# OpenStage.net
KiCad netlist of a schematic drawn in EAGLE
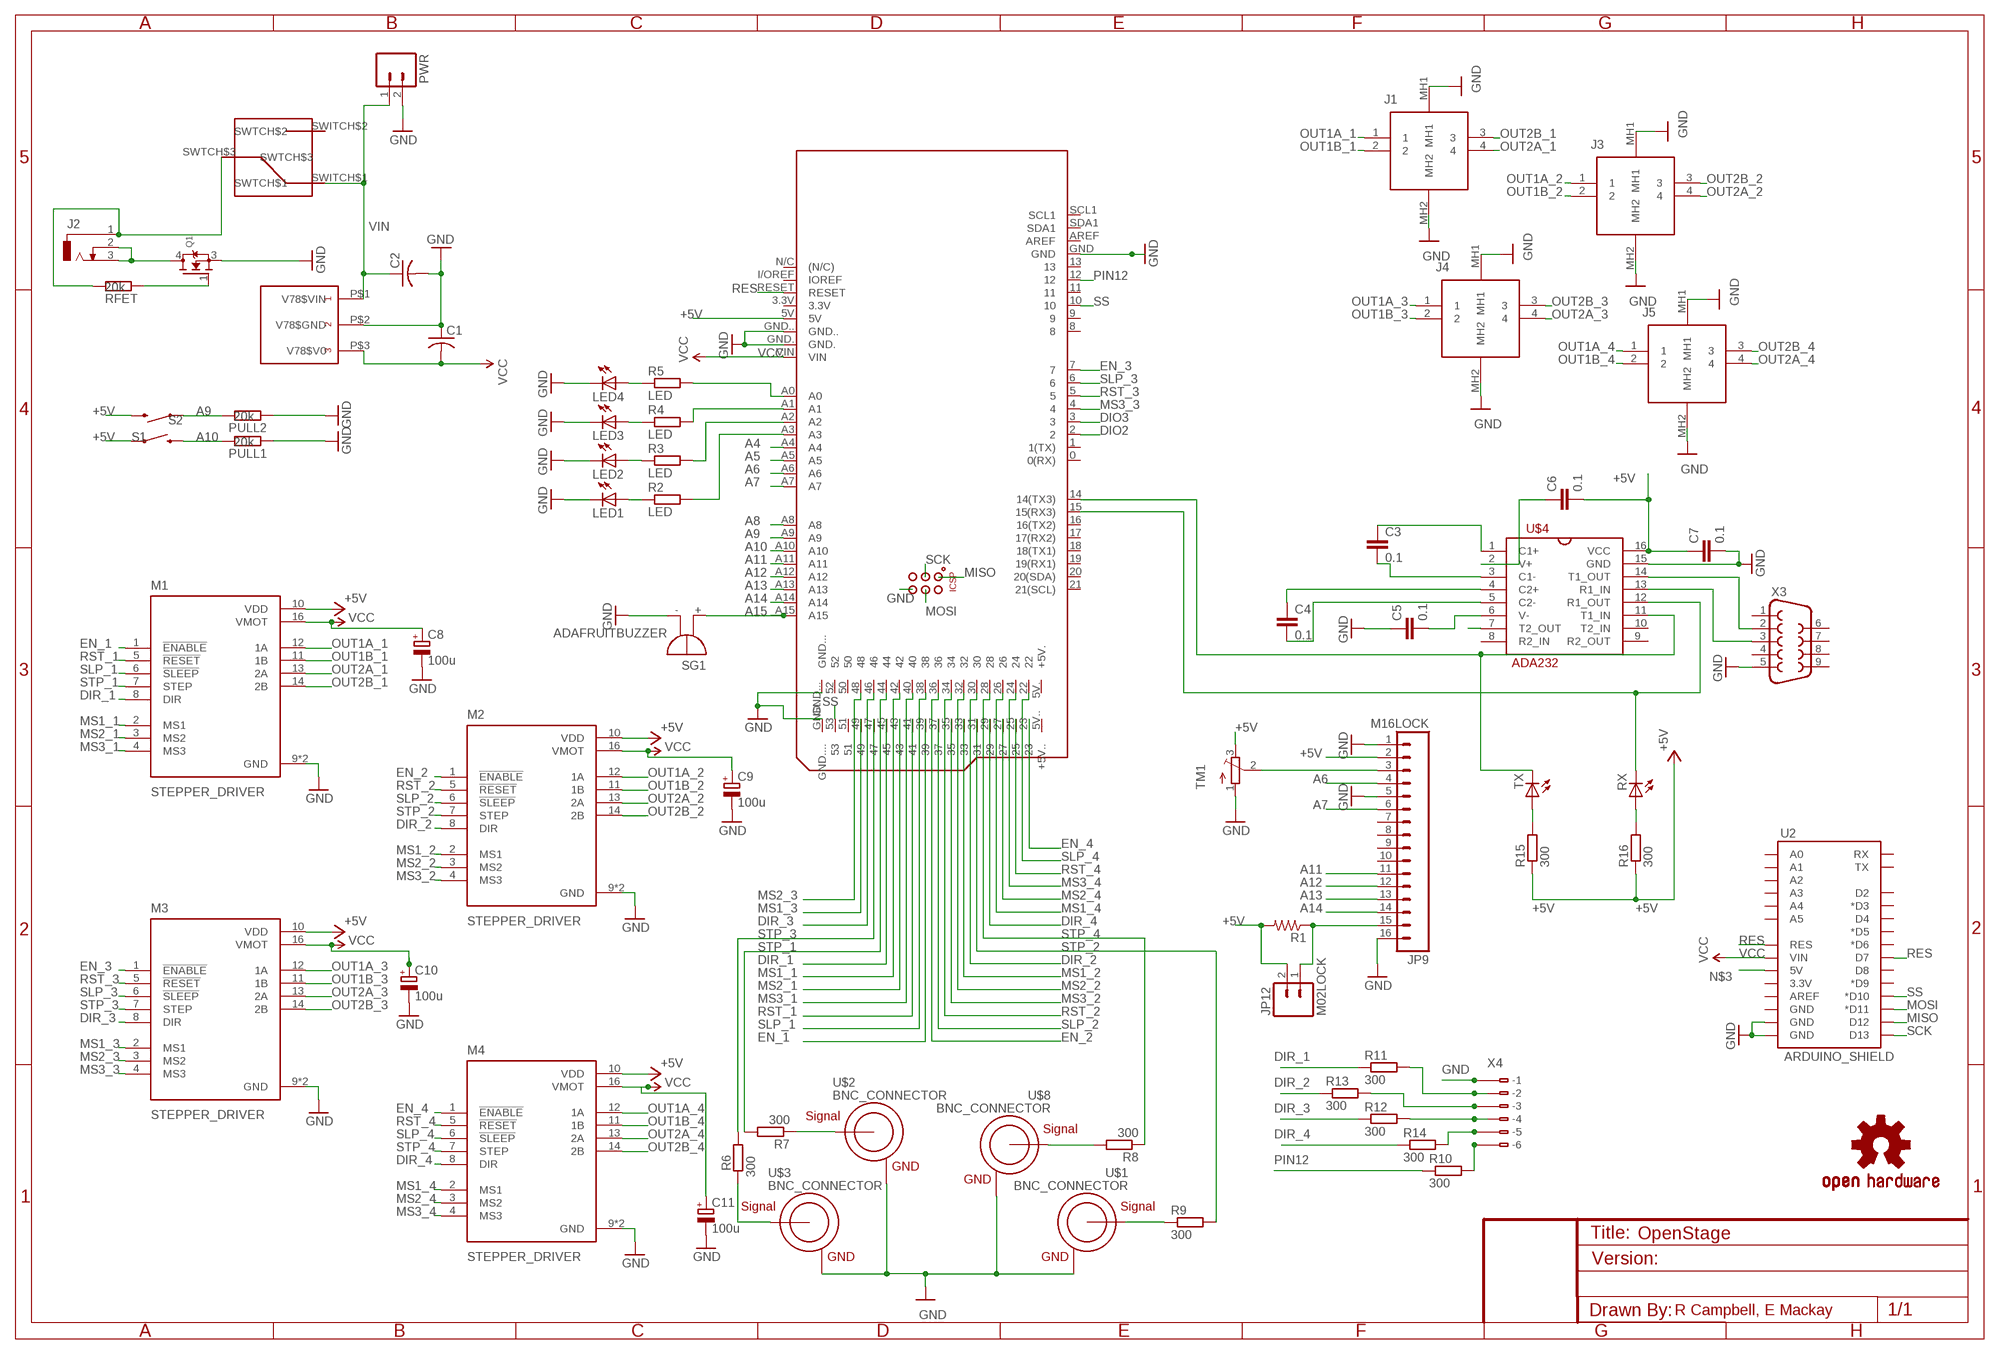
[diagram p0: schematic, sheet 1]

(export (version "E")
  (design (tool "Eeschema 10.0.6"))
  (components
    (comp (ref "C1")
      (value "C-USC1210K")
      (footprint "eagle-import:C1210K")
      (libsource (lib "eagle-import") (part "C-USC1210K"))
    )
    (comp (ref "C2")
      (value "C-USC1210K")
      (footprint "eagle-import:C1210K")
      (libsource (lib "eagle-import") (part "C-USC1210K"))
    )
    (comp (ref "C3")
      (value "0.1")
      (footprint "eagle-import:AXIAL-5MM")
      (libsource (lib "eagle-import") (part "CAP_"))
    )
    (comp (ref "C4")
      (value "0.1")
      (footprint "eagle-import:AXIAL-5MM")
      (libsource (lib "eagle-import") (part "CAP_"))
    )
    (comp (ref "C5")
      (value "0.1")
      (footprint "eagle-import:AXIAL-5MM")
      (libsource (lib "eagle-import") (part "CAP_"))
    )
    (comp (ref "C6")
      (value "0.1")
      (footprint "eagle-import:AXIAL-5MM")
      (libsource (lib "eagle-import") (part "CAP_"))
    )
    (comp (ref "C7")
      (value "0.1")
      (footprint "eagle-import:AXIAL-5MM")
      (libsource (lib "eagle-import") (part "CAP_"))
    )
    (comp (ref "C8")
      (value "100u")
      (footprint "eagle-import:E2,5-5")
      (libsource (lib "eagle-import") (part "CPOL-EUE2.5-5"))
    )
    (comp (ref "C9")
      (value "100u")
      (footprint "eagle-import:E2,5-5")
      (libsource (lib "eagle-import") (part "CPOL-EUE2.5-5"))
    )
    (comp (ref "C10")
      (value "100u")
      (footprint "eagle-import:E2,5-5")
      (libsource (lib "eagle-import") (part "CPOL-EUE2.5-5"))
    )
    (comp (ref "C11")
      (value "100u")
      (footprint "eagle-import:E2,5-5")
      (libsource (lib "eagle-import") (part "CPOL-EUE2.5-5"))
    )
    (comp (ref "J1")
      (value "M8S-04PFFR-SF8001")
      (footprint "eagle-import:M8S04PFFRSF8001")
      (fields (field (name "MOUSER_PART_NUMBER") "523-M8S04PFFRSF8001"))
      (libsource (lib "eagle-import") (part "M8S-04PFFR-SF8001"))
    )
    (comp (ref "J2")
      (value "DCJ0303")
      (footprint "eagle-import:DCJ0303")
      (libsource (lib "eagle-import") (part "DCJ0303"))
    )
    (comp (ref "J3")
      (value "M8S-04PFFR-SF8001")
      (footprint "eagle-import:M8S04PFFRSF8001")
      (fields (field (name "MOUSER_PART_NUMBER") "523-M8S04PFFRSF8001"))
      (libsource (lib "eagle-import") (part "M8S-04PFFR-SF8001"))
    )
    (comp (ref "J4")
      (value "M8S-04PFFR-SF8001")
      (footprint "eagle-import:M8S04PFFRSF8001")
      (fields (field (name "MOUSER_PART_NUMBER") "523-M8S04PFFRSF8001"))
      (libsource (lib "eagle-import") (part "M8S-04PFFR-SF8001"))
    )
    (comp (ref "J5")
      (value "M8S-04PFFR-SF8001")
      (footprint "eagle-import:M8S04PFFRSF8001")
      (fields (field (name "MOUSER_PART_NUMBER") "523-M8S04PFFRSF8001"))
      (libsource (lib "eagle-import") (part "M8S-04PFFR-SF8001"))
    )
    (comp (ref "JP9")
      (value "M16LOCK")
      (footprint "eagle-import:1X16_LOCK")
      (libsource (lib "eagle-import") (part "M16LOCK"))
    )
    (comp (ref "JP12")
      (value "M02LOCK")
      (footprint "eagle-import:1X02_LOCK")
      (libsource (lib "eagle-import") (part "SparkFun-Connectors_M02LOCK"))
    )
    (comp (ref "LED1")
      (value "LED3MM")
      (footprint "eagle-import:LED3MM")
      (libsource (lib "eagle-import") (part "LED3MM"))
    )
    (comp (ref "LED2")
      (value "LED3MM")
      (footprint "eagle-import:LED3MM")
      (libsource (lib "eagle-import") (part "LED3MM"))
    )
    (comp (ref "LED3")
      (value "LED3MM")
      (footprint "eagle-import:LED3MM")
      (libsource (lib "eagle-import") (part "LED3MM"))
    )
    (comp (ref "LED4")
      (value "LED3MM")
      (footprint "eagle-import:LED3MM")
      (libsource (lib "eagle-import") (part "LED3MM"))
    )
    (comp (ref "LOGO1")
      (value "OSHW-LOGOL")
      (footprint "eagle-import:OSHW-LOGO-L")
      (libsource (lib "eagle-import") (part "OSHW-LOGOL"))
    )
    (comp (ref "M1")
      (value "STEPPER_DRIVER")
      (footprint "eagle-import:POLOLU_CARRIER")
      (fields (field (name "MF") "Pololu") (field (name "MP") "A4988 STEPPER MOTOR DRIVER CARRIER"))
      (libsource (lib "eagle-import") (part "STEPPER_DRIVER"))
    )
    (comp (ref "M2")
      (value "STEPPER_DRIVER")
      (footprint "eagle-import:POLOLU_CARRIER")
      (fields (field (name "MF") "Pololu") (field (name "MP") "A4988 STEPPER MOTOR DRIVER CARRIER"))
      (libsource (lib "eagle-import") (part "STEPPER_DRIVER"))
    )
    (comp (ref "M3")
      (value "STEPPER_DRIVER")
      (footprint "eagle-import:POLOLU_CARRIER")
      (fields (field (name "MF") "Pololu") (field (name "MP") "A4988 STEPPER MOTOR DRIVER CARRIER"))
      (libsource (lib "eagle-import") (part "STEPPER_DRIVER"))
    )
    (comp (ref "M4")
      (value "STEPPER_DRIVER")
      (footprint "eagle-import:POLOLU_CARRIER")
      (fields (field (name "MF") "Pololu") (field (name "MP") "A4988 STEPPER MOTOR DRIVER CARRIER"))
      (libsource (lib "eagle-import") (part "STEPPER_DRIVER"))
    )
    (comp (ref "PCB2")
      (value "ARDUINO_MEGA_ROB")
      (footprint "eagle-import:ARDUINO_MEGA_ROB")
      (libsource (lib "eagle-import") (part "ARDUINO_MEGA_ROB"))
    )
    (comp (ref "PULL1")
      (value "20k")
      (footprint "eagle-import:R3216")
      (libsource (lib "eagle-import") (part "R-EU_R3216"))
    )
    (comp (ref "PULL2")
      (value "20k")
      (footprint "eagle-import:R3216")
      (libsource (lib "eagle-import") (part "R-EU_R3216"))
    )
    (comp (ref "PWR")
      (value "M02PTH")
      (footprint "eagle-import:1X02")
      (libsource (lib "eagle-import") (part "M02PTH"))
    )
    (comp (ref "Q1")
      (value "MOSFET-N_TO252")
      (footprint "eagle-import:TO252")
      (libsource (lib "eagle-import") (part "MOSFET-N_TO252"))
    )
    (comp (ref "R1")
      (value "R-US_0204/7")
      (footprint "eagle-import:0204_7")
      (libsource (lib "eagle-import") (part "R-US_0204/7"))
    )
    (comp (ref "R2")
      (value "LED")
      (footprint "eagle-import:R3216")
      (libsource (lib "eagle-import") (part "R-EU_R3216"))
    )
    (comp (ref "R3")
      (value "LED")
      (footprint "eagle-import:R3216")
      (libsource (lib "eagle-import") (part "R-EU_R3216"))
    )
    (comp (ref "R4")
      (value "LED")
      (footprint "eagle-import:R3216")
      (libsource (lib "eagle-import") (part "R-EU_R3216"))
    )
    (comp (ref "R5")
      (value "LED")
      (footprint "eagle-import:R3216")
      (libsource (lib "eagle-import") (part "R-EU_R3216"))
    )
    (comp (ref "R6")
      (value "300")
      (footprint "eagle-import:R3216")
      (libsource (lib "eagle-import") (part "R-EU_R3216"))
    )
    (comp (ref "R7")
      (value "300")
      (footprint "eagle-import:R3216")
      (libsource (lib "eagle-import") (part "R-EU_R3216"))
    )
    (comp (ref "R8")
      (value "300")
      (footprint "eagle-import:R3216")
      (libsource (lib "eagle-import") (part "R-EU_R3216"))
    )
    (comp (ref "R9")
      (value "300")
      (footprint "eagle-import:R3216")
      (libsource (lib "eagle-import") (part "R-EU_R3216"))
    )
    (comp (ref "R10")
      (value "300")
      (footprint "eagle-import:R3216")
      (libsource (lib "eagle-import") (part "R-EU_R3216"))
    )
    (comp (ref "R11")
      (value "300")
      (footprint "eagle-import:R3216")
      (libsource (lib "eagle-import") (part "R-EU_R3216"))
    )
    (comp (ref "R12")
      (value "300")
      (footprint "eagle-import:R3216")
      (libsource (lib "eagle-import") (part "R-EU_R3216"))
    )
    (comp (ref "R13")
      (value "300")
      (footprint "eagle-import:R3216")
      (libsource (lib "eagle-import") (part "R-EU_R3216"))
    )
    (comp (ref "R14")
      (value "300")
      (footprint "eagle-import:R3216")
      (libsource (lib "eagle-import") (part "R-EU_R3216"))
    )
    (comp (ref "R15")
      (value "300")
      (footprint "eagle-import:R3216")
      (libsource (lib "eagle-import") (part "R-EU_R3216"))
    )
    (comp (ref "R16")
      (value "300")
      (footprint "eagle-import:R3216")
      (libsource (lib "eagle-import") (part "R-EU_R3216"))
    )
    (comp (ref "RFET")
      (value "20k")
      (footprint "eagle-import:R3216")
      (libsource (lib "eagle-import") (part "R-EU_R3216"))
    )
    (comp (ref "RX")
      (value "LED3MM")
      (footprint "eagle-import:LED3MM")
      (libsource (lib "eagle-import") (part "LED3MM"))
    )
    (comp (ref "S1")
      (value "SWITCH-MOMENTARY-212MM")
      (footprint "eagle-import:TACTILE-PTH-12MM")
      (libsource (lib "eagle-import") (part "SWITCH-MOMENTARY-212MM"))
    )
    (comp (ref "S2")
      (value "SWITCH-MOMENTARY-212MM")
      (footprint "eagle-import:TACTILE-PTH-12MM")
      (libsource (lib "eagle-import") (part "SWITCH-MOMENTARY-212MM"))
    )
    (comp (ref "SG1")
      (value "ADAFRUITBUZZER")
      (footprint "eagle-import:BMT1205XH7.5")
      (libsource (lib "eagle-import") (part "ADAFRUITBUZZER"))
    )
    (comp (ref "TM1")
      (value "TRIMPOT3386")
      (footprint "eagle-import:TRIM-3386")
      (libsource (lib "eagle-import") (part "TRIMPOT3386"))
    )
    (comp (ref "TX")
      (value "LED3MM")
      (footprint "eagle-import:LED3MM")
      (libsource (lib "eagle-import") (part "LED3MM"))
    )
    (comp (ref "U$1")
      (value "BNC_CONNECTOR")
      (footprint "eagle-import:BNC_CONNECTOR")
      (libsource (lib "eagle-import") (part "BNC_CONNECTOR"))
    )
    (comp (ref "U$2")
      (value "BNC_CONNECTOR")
      (footprint "eagle-import:BNC_CONNECTOR")
      (libsource (lib "eagle-import") (part "BNC_CONNECTOR"))
    )
    (comp (ref "U$3")
      (value "BNC_CONNECTOR")
      (footprint "eagle-import:BNC_CONNECTOR")
      (libsource (lib "eagle-import") (part "BNC_CONNECTOR"))
    )
    (comp (ref "U$4")
      (value "ADA232")
      (footprint "eagle-import:DIL16")
      (libsource (lib "eagle-import") (part "ADA232"))
    )
    (comp (ref "U$5")
      (value "V78XX-1000")
      (footprint "eagle-import:V78XX-1000")
      (libsource (lib "eagle-import") (part "V78XX-1000"))
    )
    (comp (ref "U$6")
      (value "SLIDING_SWITCH_0.185")
      (footprint "eagle-import:SLIDING_SWITCH_0.185")
      (libsource (lib "eagle-import") (part "SLIDING_SWITCH_0.185"))
    )
    (comp (ref "U$8")
      (value "BNC_CONNECTOR")
      (footprint "eagle-import:BNC_CONNECTOR")
      (libsource (lib "eagle-import") (part "BNC_CONNECTOR"))
    )
    (comp (ref "U2")
      (value "ARDUINO_SHIELD")
      (footprint "eagle-import:DUEMILANOVE_VIAS")
      (libsource (lib "eagle-import") (part "ARDUINO_SHIELDNO_SILK"))
    )
    (comp (ref "X3")
      (value "DB9FEMALE")
      (footprint "eagle-import:DB9")
      (libsource (lib "eagle-import") (part "DB9FEMALE"))
    )
    (comp (ref "X4")
      (value "233-206")
      (footprint "eagle-import:233-206")
      (libsource (lib "eagle-import") (part "233-206"))
    )
  )
  (nets
    (net (code "1") (name "+5V") (class "Default")
      (node (ref "C6") (pin "P$2") (pinfunction "2_P$2") (pintype "passive"))
      (node (ref "C7") (pin "P$1") (pinfunction "1_P$1") (pintype "passive"))
      (node (ref "JP12") (pin "2") (pinfunction "2_2") (pintype "passive"))
      (node (ref "JP9") (pin "2") (pinfunction "2_2") (pintype "passive"))
      (node (ref "M1") (pin "10") (pinfunction "VDD_10") (pintype "power_in"))
      (node (ref "M2") (pin "10") (pinfunction "VDD_10") (pintype "power_in"))
      (node (ref "M3") (pin "10") (pinfunction "VDD_10") (pintype "power_in"))
      (node (ref "M4") (pin "10") (pinfunction "VDD_10") (pintype "power_in"))
      (node (ref "PCB2") (pin "5V") (pinfunction "5V_5V") (pintype "bidirectional"))
      (node (ref "R1") (pin "2") (pinfunction "2_2") (pintype "passive"))
      (node (ref "R15") (pin "1") (pinfunction "1_1") (pintype "passive"))
      (node (ref "R16") (pin "1") (pinfunction "1_1") (pintype "passive"))
      (node (ref "S1") (pin "1") (pinfunction "1_1") (pintype "passive"))
      (node (ref "S2") (pin "3") (pinfunction "2_3") (pintype "passive"))
      (node (ref "TM1") (pin "3") (pinfunction "E_3") (pintype "passive"))
      (node (ref "U$4") (pin "16") (pinfunction "VCC_16") (pintype "bidirectional"))
    )
    (net (code "2") (name "/A4") (class "Default")
      (node (ref "PCB2") (pin "A4") (pinfunction "A4_A4") (pintype "bidirectional"))
    )
    (net (code "3") (name "/A5") (class "Default")
      (node (ref "PCB2") (pin "A5") (pinfunction "A5_A5") (pintype "bidirectional"))
    )
    (net (code "4") (name "/A6") (class "Default")
      (node (ref "JP9") (pin "4") (pinfunction "4_4") (pintype "passive"))
      (node (ref "PCB2") (pin "A6") (pinfunction "A6_A6") (pintype "bidirectional"))
    )
    (net (code "5") (name "/A7") (class "Default")
      (node (ref "JP9") (pin "6") (pinfunction "6_6") (pintype "passive"))
      (node (ref "PCB2") (pin "A7") (pinfunction "A7_A7") (pintype "bidirectional"))
    )
    (net (code "6") (name "/A8") (class "Default")
      (node (ref "PCB2") (pin "A8") (pinfunction "A8_A8") (pintype "bidirectional"))
    )
    (net (code "7") (name "/A9") (class "Default")
      (node (ref "PCB2") (pin "A9") (pinfunction "A9_A9") (pintype "bidirectional"))
      (node (ref "PULL2") (pin "2") (pinfunction "2_2") (pintype "passive"))
      (node (ref "S2") (pin "1") (pinfunction "1_1") (pintype "passive"))
    )
    (net (code "8") (name "/A10") (class "Default")
      (node (ref "PCB2") (pin "A10") (pinfunction "A10_A10") (pintype "bidirectional"))
      (node (ref "PULL1") (pin "2") (pinfunction "2_2") (pintype "passive"))
      (node (ref "S1") (pin "3") (pinfunction "2_3") (pintype "passive"))
    )
    (net (code "9") (name "/A11") (class "Default")
      (node (ref "JP9") (pin "11") (pinfunction "11_11") (pintype "passive"))
      (node (ref "PCB2") (pin "A11") (pinfunction "A11_A11") (pintype "bidirectional"))
    )
    (net (code "10") (name "/A12") (class "Default")
      (node (ref "JP9") (pin "12") (pinfunction "12_12") (pintype "passive"))
      (node (ref "PCB2") (pin "A12") (pinfunction "A12_A12") (pintype "bidirectional"))
    )
    (net (code "11") (name "/A13") (class "Default")
      (node (ref "JP9") (pin "13") (pinfunction "13_13") (pintype "passive"))
      (node (ref "PCB2") (pin "A13") (pinfunction "A13_A13") (pintype "bidirectional"))
    )
    (net (code "12") (name "/A14") (class "Default")
      (node (ref "JP9") (pin "14") (pinfunction "14_14") (pintype "passive"))
      (node (ref "PCB2") (pin "A14") (pinfunction "A14_A14") (pintype "bidirectional"))
    )
    (net (code "13") (name "/A15") (class "Default")
      (node (ref "PCB2") (pin "A15") (pinfunction "A15_A15") (pintype "bidirectional"))
      (node (ref "SG1") (pin "+") (pinfunction "+_+") (pintype "passive"))
    )
    (net (code "14") (name "/DIO2") (class "Default")
      (node (ref "PCB2") (pin "2") (pinfunction "2_2") (pintype "bidirectional"))
    )
    (net (code "15") (name "/DIO3") (class "Default")
      (node (ref "PCB2") (pin "3") (pinfunction "3_3") (pintype "bidirectional"))
    )
    (net (code "16") (name "/DIR_1") (class "Default")
      (node (ref "M1") (pin "8") (pinfunction "DIR_8") (pintype "input"))
      (node (ref "PCB2") (pin "45") (pinfunction "45_45") (pintype "bidirectional"))
      (node (ref "R11") (pin "1") (pinfunction "1_1") (pintype "passive"))
    )
    (net (code "17") (name "/DIR_2") (class "Default")
      (node (ref "M2") (pin "8") (pinfunction "DIR_8") (pintype "input"))
      (node (ref "PCB2") (pin "30") (pinfunction "30_30") (pintype "bidirectional"))
      (node (ref "R13") (pin "1") (pinfunction "1_1") (pintype "passive"))
    )
    (net (code "18") (name "/DIR_3") (class "Default")
      (node (ref "M3") (pin "8") (pinfunction "DIR_8") (pintype "input"))
      (node (ref "PCB2") (pin "46") (pinfunction "46_46") (pintype "bidirectional"))
      (node (ref "R12") (pin "1") (pinfunction "1_1") (pintype "passive"))
    )
    (net (code "19") (name "/DIR_4") (class "Default")
      (node (ref "M4") (pin "8") (pinfunction "DIR_8") (pintype "input"))
      (node (ref "PCB2") (pin "29") (pinfunction "29_29") (pintype "bidirectional"))
      (node (ref "R14") (pin "1") (pinfunction "1_1") (pintype "passive"))
    )
    (net (code "20") (name "/EN_1") (class "Default")
      (node (ref "M1") (pin "1") (pinfunction "~{ENABLE}_1") (pintype "input"))
      (node (ref "PCB2") (pin "39") (pinfunction "39_39") (pintype "bidirectional"))
    )
    (net (code "21") (name "/EN_2") (class "Default")
      (node (ref "M2") (pin "1") (pinfunction "~{ENABLE}_1") (pintype "input"))
      (node (ref "PCB2") (pin "36") (pinfunction "36_36") (pintype "bidirectional"))
    )
    (net (code "22") (name "/EN_3") (class "Default")
      (node (ref "M3") (pin "1") (pinfunction "~{ENABLE}_1") (pintype "input"))
      (node (ref "PCB2") (pin "7") (pinfunction "7_7") (pintype "bidirectional"))
    )
    (net (code "23") (name "/EN_4") (class "Default")
      (node (ref "M4") (pin "1") (pinfunction "~{ENABLE}_1") (pintype "input"))
      (node (ref "PCB2") (pin "23") (pinfunction "23_23") (pintype "bidirectional"))
    )
    (net (code "24") (name "/MISO") (class "Default")
      (node (ref "PCB2") (pin "MISO") (pinfunction "MISO_MISO") (pintype "bidirectional"))
      (node (ref "U2") (pin "D12") (pinfunction "D12_D12") (pintype "bidirectional"))
    )
    (net (code "25") (name "/MOSI") (class "Default")
      (node (ref "PCB2") (pin "MOSI") (pinfunction "MOSI_MOSI") (pintype "bidirectional"))
      (node (ref "U2") (pin "D11") (pinfunction "*D11_D11") (pintype "bidirectional"))
    )
    (net (code "26") (name "/MS1_1") (class "Default")
      (node (ref "M1") (pin "2") (pinfunction "MS1_2") (pintype "input"))
      (node (ref "PCB2") (pin "42") (pinfunction "42_42") (pintype "bidirectional"))
    )
    (net (code "27") (name "/MS1_2") (class "Default")
      (node (ref "M2") (pin "2") (pinfunction "MS1_2") (pintype "input"))
      (node (ref "PCB2") (pin "33") (pinfunction "33_33") (pintype "bidirectional"))
    )
    (net (code "28") (name "/MS1_3") (class "Default")
      (node (ref "M3") (pin "2") (pinfunction "MS1_2") (pintype "input"))
      (node (ref "PCB2") (pin "49") (pinfunction "49_49") (pintype "bidirectional"))
    )
    (net (code "29") (name "/MS1_4") (class "Default")
      (node (ref "M4") (pin "2") (pinfunction "MS1_2") (pintype "input"))
      (node (ref "PCB2") (pin "26") (pinfunction "26_26") (pintype "bidirectional"))
    )
    (net (code "30") (name "/MS2_1") (class "Default")
      (node (ref "M1") (pin "3") (pinfunction "MS2_3") (pintype "input"))
      (node (ref "PCB2") (pin "43") (pinfunction "43_43") (pintype "bidirectional"))
    )
    (net (code "31") (name "/MS2_2") (class "Default")
      (node (ref "M2") (pin "3") (pinfunction "MS2_3") (pintype "input"))
      (node (ref "PCB2") (pin "32") (pinfunction "32_32") (pintype "bidirectional"))
    )
    (net (code "32") (name "/MS2_3") (class "Default")
      (node (ref "M3") (pin "3") (pinfunction "MS2_3") (pintype "input"))
      (node (ref "PCB2") (pin "48") (pinfunction "48_48") (pintype "bidirectional"))
    )
    (net (code "33") (name "/MS2_4") (class "Default")
      (node (ref "M4") (pin "3") (pinfunction "MS2_3") (pintype "input"))
      (node (ref "PCB2") (pin "27") (pinfunction "27_27") (pintype "bidirectional"))
    )
    (net (code "34") (name "/MS3_1") (class "Default")
      (node (ref "M1") (pin "4") (pinfunction "MS3_4") (pintype "input"))
      (node (ref "PCB2") (pin "40") (pinfunction "40_40") (pintype "bidirectional"))
    )
    (net (code "35") (name "/MS3_2") (class "Default")
      (node (ref "M2") (pin "4") (pinfunction "MS3_4") (pintype "input"))
      (node (ref "PCB2") (pin "35") (pinfunction "35_35") (pintype "bidirectional"))
    )
    (net (code "36") (name "/MS3_3") (class "Default")
      (node (ref "M3") (pin "4") (pinfunction "MS3_4") (pintype "input"))
      (node (ref "PCB2") (pin "4") (pinfunction "4_4") (pintype "bidirectional"))
    )
    (net (code "37") (name "/MS3_4") (class "Default")
      (node (ref "M4") (pin "4") (pinfunction "MS3_4") (pintype "input"))
      (node (ref "PCB2") (pin "24") (pinfunction "24_24") (pintype "bidirectional"))
    )
    (net (code "38") (name "/N$3") (class "Default")
      (node (ref "U2") (pin "5V") (pinfunction "5V_5V") (pintype "bidirectional"))
    )
    (net (code "39") (name "/OUT1A_1") (class "Default")
      (node (ref "J1") (pin "1") (pinfunction "1_1") (pintype "bidirectional"))
      (node (ref "M1") (pin "12") (pinfunction "1A_12") (pintype "output"))
    )
    (net (code "40") (name "/OUT1A_2") (class "Default")
      (node (ref "J3") (pin "1") (pinfunction "1_1") (pintype "bidirectional"))
      (node (ref "M2") (pin "12") (pinfunction "1A_12") (pintype "output"))
    )
    (net (code "41") (name "/OUT1A_3") (class "Default")
      (node (ref "J4") (pin "1") (pinfunction "1_1") (pintype "bidirectional"))
      (node (ref "M3") (pin "12") (pinfunction "1A_12") (pintype "output"))
    )
    (net (code "42") (name "/OUT1A_4") (class "Default")
      (node (ref "J5") (pin "1") (pinfunction "1_1") (pintype "bidirectional"))
      (node (ref "M4") (pin "12") (pinfunction "1A_12") (pintype "output"))
    )
    (net (code "43") (name "/OUT1B_1") (class "Default")
      (node (ref "J1") (pin "2") (pinfunction "2_2") (pintype "bidirectional"))
      (node (ref "M1") (pin "11") (pinfunction "1B_11") (pintype "output"))
    )
    (net (code "44") (name "/OUT1B_2") (class "Default")
      (node (ref "J3") (pin "2") (pinfunction "2_2") (pintype "bidirectional"))
      (node (ref "M2") (pin "11") (pinfunction "1B_11") (pintype "output"))
    )
    (net (code "45") (name "/OUT1B_3") (class "Default")
      (node (ref "J4") (pin "2") (pinfunction "2_2") (pintype "bidirectional"))
      (node (ref "M3") (pin "11") (pinfunction "1B_11") (pintype "output"))
    )
    (net (code "46") (name "/OUT1B_4") (class "Default")
      (node (ref "J5") (pin "2") (pinfunction "2_2") (pintype "bidirectional"))
      (node (ref "M4") (pin "11") (pinfunction "1B_11") (pintype "output"))
    )
    (net (code "47") (name "/OUT2A_1") (class "Default")
      (node (ref "J1") (pin "4") (pinfunction "4_4") (pintype "bidirectional"))
      (node (ref "M1") (pin "13") (pinfunction "2A_13") (pintype "output"))
    )
    (net (code "48") (name "/OUT2A_2") (class "Default")
      (node (ref "J3") (pin "4") (pinfunction "4_4") (pintype "bidirectional"))
      (node (ref "M2") (pin "13") (pinfunction "2A_13") (pintype "output"))
    )
    (net (code "49") (name "/OUT2A_3") (class "Default")
      (node (ref "J4") (pin "4") (pinfunction "4_4") (pintype "bidirectional"))
      (node (ref "M3") (pin "13") (pinfunction "2A_13") (pintype "output"))
    )
    (net (code "50") (name "/OUT2A_4") (class "Default")
      (node (ref "J5") (pin "4") (pinfunction "4_4") (pintype "bidirectional"))
      (node (ref "M4") (pin "13") (pinfunction "2A_13") (pintype "output"))
    )
    (net (code "51") (name "/OUT2B_1") (class "Default")
      (node (ref "J1") (pin "3") (pinfunction "3_3") (pintype "bidirectional"))
      (node (ref "M1") (pin "14") (pinfunction "2B_14") (pintype "output"))
    )
    (net (code "52") (name "/OUT2B_2") (class "Default")
      (node (ref "J3") (pin "3") (pinfunction "3_3") (pintype "bidirectional"))
      (node (ref "M2") (pin "14") (pinfunction "2B_14") (pintype "output"))
    )
    (net (code "53") (name "/OUT2B_3") (class "Default")
      (node (ref "J4") (pin "3") (pinfunction "3_3") (pintype "bidirectional"))
      (node (ref "M3") (pin "14") (pinfunction "2B_14") (pintype "output"))
    )
    (net (code "54") (name "/OUT2B_4") (class "Default")
      (node (ref "J5") (pin "3") (pinfunction "3_3") (pintype "bidirectional"))
      (node (ref "M4") (pin "14") (pinfunction "2B_14") (pintype "output"))
    )
    (net (code "55") (name "/PIN12") (class "Default")
      (node (ref "PCB2") (pin "12") (pinfunction "12_12") (pintype "bidirectional"))
      (node (ref "R10") (pin "1") (pinfunction "1_1") (pintype "passive"))
    )
    (net (code "56") (name "/RES") (class "Default")
      (node (ref "PCB2") (pin "RESET") (pinfunction "RESET_RESET") (pintype "bidirectional"))
      (node (ref "U2") (pin "D7") (pinfunction "D7_D7") (pintype "bidirectional"))
      (node (ref "U2") (pin "RES") (pinfunction "RES_RES") (pintype "bidirectional"))
    )
    (net (code "57") (name "/RST_1") (class "Default")
      (node (ref "M1") (pin "5") (pinfunction "~{RESET}_5") (pintype "input"))
      (node (ref "PCB2") (pin "41") (pinfunction "41_41") (pintype "bidirectional"))
    )
    (net (code "58") (name "/RST_2") (class "Default")
      (node (ref "M2") (pin "5") (pinfunction "~{RESET}_5") (pintype "input"))
      (node (ref "PCB2") (pin "34") (pinfunction "34_34") (pintype "bidirectional"))
    )
    (net (code "59") (name "/RST_3") (class "Default")
      (node (ref "M3") (pin "5") (pinfunction "~{RESET}_5") (pintype "input"))
      (node (ref "PCB2") (pin "5") (pinfunction "5_5") (pintype "bidirectional"))
    )
    (net (code "60") (name "/RST_4") (class "Default")
      (node (ref "M4") (pin "5") (pinfunction "~{RESET}_5") (pintype "input"))
      (node (ref "PCB2") (pin "25") (pinfunction "25_25") (pintype "bidirectional"))
    )
    (net (code "61") (name "/SCK") (class "Default")
      (node (ref "PCB2") (pin "SCK") (pinfunction "SCK_SCK") (pintype "bidirectional"))
      (node (ref "U2") (pin "D13") (pinfunction "D13_D13") (pintype "bidirectional"))
    )
    (net (code "62") (name "/SLP_1") (class "Default")
      (node (ref "M1") (pin "6") (pinfunction "~{SLEEP}_6") (pintype "input"))
      (node (ref "PCB2") (pin "38") (pinfunction "38_38") (pintype "bidirectional"))
    )
    (net (code "63") (name "/SLP_2") (class "Default")
      (node (ref "M2") (pin "6") (pinfunction "~{SLEEP}_6") (pintype "input"))
      (node (ref "PCB2") (pin "37") (pinfunction "37_37") (pintype "bidirectional"))
    )
    (net (code "64") (name "/SLP_3") (class "Default")
      (node (ref "M3") (pin "6") (pinfunction "~{SLEEP}_6") (pintype "input"))
      (node (ref "PCB2") (pin "6") (pinfunction "6_6") (pintype "bidirectional"))
    )
    (net (code "65") (name "/SLP_4") (class "Default")
      (node (ref "M4") (pin "6") (pinfunction "~{SLEEP}_6") (pintype "input"))
      (node (ref "PCB2") (pin "22") (pinfunction "22_22") (pintype "bidirectional"))
    )
    (net (code "66") (name "/SS") (class "Default")
      (node (ref "PCB2") (pin "10") (pinfunction "10_10") (pintype "bidirectional"))
      (node (ref "PCB2") (pin "53") (pinfunction "53_53") (pintype "bidirectional"))
      (node (ref "U2") (pin "D10") (pinfunction "*D10_D10") (pintype "bidirectional"))
    )
    (net (code "67") (name "/STP_1") (class "Default")
      (node (ref "M1") (pin "7") (pinfunction "STEP_7") (pintype "input"))
      (node (ref "PCB2") (pin "44") (pinfunction "44_44") (pintype "bidirectional"))
      (node (ref "R7") (pin "2") (pinfunction "2_2") (pintype "passive"))
    )
    (net (code "68") (name "/STP_2") (class "Default")
      (node (ref "M2") (pin "7") (pinfunction "STEP_7") (pintype "input"))
      (node (ref "PCB2") (pin "31") (pinfunction "31_31") (pintype "bidirectional"))
      (node (ref "R9") (pin "2") (pinfunction "2_2") (pintype "passive"))
    )
    (net (code "69") (name "/STP_3") (class "Default")
      (node (ref "M3") (pin "7") (pinfunction "STEP_7") (pintype "input"))
      (node (ref "PCB2") (pin "47") (pinfunction "47_47") (pintype "bidirectional"))
      (node (ref "R6") (pin "2") (pinfunction "2_2") (pintype "passive"))
    )
    (net (code "70") (name "/STP_4") (class "Default")
      (node (ref "M4") (pin "7") (pinfunction "STEP_7") (pintype "input"))
      (node (ref "PCB2") (pin "28") (pinfunction "28_28") (pintype "bidirectional"))
      (node (ref "R8") (pin "1") (pinfunction "1_1") (pintype "passive"))
    )
    (net (code "71") (name "/VIN") (class "Default")
      (node (ref "C2") (pin "1") (pinfunction "1_1") (pintype "passive"))
      (node (ref "PWR") (pin "1") (pinfunction "1_1") (pintype "passive"))
      (node (ref "U$5") (pin "P$1") (pinfunction "V78$VIN_P$1") (pintype "bidirectional"))
      (node (ref "U$6") (pin "SWITCH$1") (pinfunction "SWTCH$1_SWITCH$1") (pintype "bidirectional"))
    )
    (net (code "72") (name "GND") (class "Default")
      (node (ref "C1") (pin "1") (pinfunction "1_1") (pintype "passive"))
      (node (ref "C10") (pin "-") (pinfunction "-_-") (pintype "passive"))
      (node (ref "C11") (pin "-") (pinfunction "-_-") (pintype "passive"))
      (node (ref "C2") (pin "2") (pinfunction "2_2") (pintype "passive"))
      (node (ref "C5") (pin "P$1") (pinfunction "1_P$1") (pintype "passive"))
      (node (ref "C7") (pin "P$2") (pinfunction "2_P$2") (pintype "passive"))
      (node (ref "C8") (pin "-") (pinfunction "-_-") (pintype "passive"))
      (node (ref "C9") (pin "-") (pinfunction "-_-") (pintype "passive"))
      (node (ref "J1") (pin "MH1") (pinfunction "MH1_MH1") (pintype "bidirectional"))
      (node (ref "J1") (pin "MH2") (pinfunction "MH2_MH2") (pintype "bidirectional"))
      (node (ref "J3") (pin "MH1") (pinfunction "MH1_MH1") (pintype "bidirectional"))
      (node (ref "J3") (pin "MH2") (pinfunction "MH2_MH2") (pintype "bidirectional"))
      (node (ref "J4") (pin "MH1") (pinfunction "MH1_MH1") (pintype "bidirectional"))
      (node (ref "J4") (pin "MH2") (pinfunction "MH2_MH2") (pintype "bidirectional"))
      (node (ref "J5") (pin "MH1") (pinfunction "MH1_MH1") (pintype "bidirectional"))
      (node (ref "J5") (pin "MH2") (pinfunction "MH2_MH2") (pintype "bidirectional"))
      (node (ref "JP9") (pin "1") (pinfunction "1_1") (pintype "passive"))
      (node (ref "JP9") (pin "16") (pinfunction "16_16") (pintype "passive"))
      (node (ref "JP9") (pin "5") (pinfunction "5_5") (pintype "passive"))
      (node (ref "LED1") (pin "K") (pinfunction "C_K") (pintype "passive"))
      (node (ref "LED2") (pin "K") (pinfunction "C_K") (pintype "passive"))
      (node (ref "LED3") (pin "K") (pinfunction "C_K") (pintype "passive"))
      (node (ref "LED4") (pin "K") (pinfunction "C_K") (pintype "passive"))
      (node (ref "M1") (pin "15") (pinfunction "GND_15") (pintype "power_in"))
      (node (ref "M1") (pin "9") (pinfunction "GND_9") (pintype "power_in"))
      (node (ref "M2") (pin "15") (pinfunction "GND_15") (pintype "power_in"))
      (node (ref "M2") (pin "9") (pinfunction "GND_9") (pintype "power_in"))
      (node (ref "M3") (pin "15") (pinfunction "GND_15") (pintype "power_in"))
      (node (ref "M3") (pin "9") (pinfunction "GND_9") (pintype "power_in"))
      (node (ref "M4") (pin "15") (pinfunction "GND_15") (pintype "power_in"))
      (node (ref "M4") (pin "9") (pinfunction "GND_9") (pintype "power_in"))
      (node (ref "PCB2") (pin "GND") (pinfunction "GND_GND") (pintype "bidirectional"))
      (node (ref "PCB2") (pin "GND.") (pinfunction "GND._GND.") (pintype "bidirectional"))
      (node (ref "PCB2") (pin "GND..") (pinfunction "GND.._GND..") (pintype "bidirectional"))
      (node (ref "PCB2") (pin "GND...") (pinfunction "GND..._GND...") (pintype "bidirectional"))
      (node (ref "PCB2") (pin "GND....") (pinfunction "GND...._GND....") (pintype "bidirectional"))
      (node (ref "PCB2") (pin "GND__") (pinfunction "GND___GND__") (pintype "bidirectional"))
      (node (ref "PULL1") (pin "1") (pinfunction "1_1") (pintype "passive"))
      (node (ref "PULL2") (pin "1") (pinfunction "1_1") (pintype "passive"))
      (node (ref "PWR") (pin "2") (pinfunction "2_2") (pintype "passive"))
      (node (ref "Q1") (pin "3") (pinfunction "S_3") (pintype "bidirectional"))
      (node (ref "SG1") (pin "-") (pinfunction "-_-") (pintype "passive"))
      (node (ref "TM1") (pin "1") (pinfunction "A_1") (pintype "passive"))
      (node (ref "U$1") (pin "GND") (pinfunction "GND_GND") (pintype "bidirectional"))
      (node (ref "U$2") (pin "GND") (pinfunction "GND_GND") (pintype "bidirectional"))
      (node (ref "U$3") (pin "GND") (pinfunction "GND_GND") (pintype "bidirectional"))
      (node (ref "U$4") (pin "15") (pinfunction "GND_15") (pintype "bidirectional"))
      (node (ref "U$5") (pin "P$2") (pinfunction "V78$GND_P$2") (pintype "bidirectional"))
      (node (ref "U$8") (pin "GND") (pinfunction "GND_GND") (pintype "bidirectional"))
      (node (ref "U2") (pin "GND@0") (pinfunction "GND_GND@0") (pintype "bidirectional"))
      (node (ref "U2") (pin "GND@1") (pinfunction "GND_GND@1") (pintype "bidirectional"))
      (node (ref "X3") (pin "5") (pinfunction "5_5") (pintype "passive"))
      (node (ref "X4") (pin "B1") (pinfunction "B-1_B1") (pintype "passive"))
    )
    (net (code "73") (name "Net-(C3-1)") (class "Default")
      (node (ref "C3") (pin "P$1") (pinfunction "1_P$1") (pintype "passive"))
      (node (ref "U$4") (pin "1") (pinfunction "C1+_1") (pintype "bidirectional"))
    )
    (net (code "74") (name "Net-(C3-2)") (class "Default")
      (node (ref "C3") (pin "P$2") (pinfunction "2_P$2") (pintype "passive"))
      (node (ref "U$4") (pin "3") (pinfunction "C1-_3") (pintype "bidirectional"))
    )
    (net (code "75") (name "Net-(C4-1)") (class "Default")
      (node (ref "C4") (pin "P$1") (pinfunction "1_P$1") (pintype "passive"))
      (node (ref "U$4") (pin "4") (pinfunction "C2+_4") (pintype "bidirectional"))
    )
    (net (code "76") (name "Net-(C4-2)") (class "Default")
      (node (ref "C4") (pin "P$2") (pinfunction "2_P$2") (pintype "passive"))
      (node (ref "U$4") (pin "5") (pinfunction "C2-_5") (pintype "bidirectional"))
    )
    (net (code "77") (name "Net-(C5-2)") (class "Default")
      (node (ref "C5") (pin "P$2") (pinfunction "2_P$2") (pintype "passive"))
      (node (ref "U$4") (pin "6") (pinfunction "V-_6") (pintype "bidirectional"))
    )
    (net (code "78") (name "Net-(C6-1)") (class "Default")
      (node (ref "C6") (pin "P$1") (pinfunction "1_P$1") (pintype "passive"))
      (node (ref "U$4") (pin "2") (pinfunction "V+_2") (pintype "bidirectional"))
    )
    (net (code "79") (name "Net-(J2-Pad1)") (class "Default")
      (node (ref "J2") (pin "1") (pinfunction "1_1") (pintype "passive"))
      (node (ref "RFET") (pin "2") (pinfunction "2_2") (pintype "passive"))
      (node (ref "U$6") (pin "SWTCH$3") (pinfunction "SWTCH$3_SWTCH$3") (pintype "bidirectional"))
    )
    (net (code "80") (name "Net-(JP12-Pad1)") (class "Default")
      (node (ref "JP12") (pin "1") (pinfunction "1_1") (pintype "passive"))
      (node (ref "JP9") (pin "15") (pinfunction "15_15") (pintype "passive"))
      (node (ref "R1") (pin "1") (pinfunction "1_1") (pintype "passive"))
    )
    (net (code "81") (name "Net-(LED1-PadA)") (class "Default")
      (node (ref "LED1") (pin "A") (pinfunction "A_A") (pintype "passive"))
      (node (ref "R2") (pin "1") (pinfunction "1_1") (pintype "passive"))
    )
    (net (code "82") (name "Net-(LED2-PadA)") (class "Default")
      (node (ref "LED2") (pin "A") (pinfunction "A_A") (pintype "passive"))
      (node (ref "R3") (pin "1") (pinfunction "1_1") (pintype "passive"))
    )
    (net (code "83") (name "Net-(LED3-PadA)") (class "Default")
      (node (ref "LED3") (pin "A") (pinfunction "A_A") (pintype "passive"))
      (node (ref "R4") (pin "1") (pinfunction "1_1") (pintype "passive"))
    )
    (net (code "84") (name "Net-(LED4-PadA)") (class "Default")
      (node (ref "LED4") (pin "A") (pinfunction "A_A") (pintype "passive"))
      (node (ref "R5") (pin "1") (pinfunction "1_1") (pintype "passive"))
    )
    (net (code "85") (name "Net-(PCB2-14(TX3))") (class "Default")
      (node (ref "PCB2") (pin "14") (pinfunction "14(TX3)_14") (pintype "bidirectional"))
      (node (ref "TX") (pin "K") (pinfunction "C_K") (pintype "passive"))
      (node (ref "U$4") (pin "11") (pinfunction "T1_IN_11") (pintype "bidirectional"))
    )
    (net (code "86") (name "Net-(PCB2-15(RX3))") (class "Default")
      (node (ref "PCB2") (pin "15") (pinfunction "15(RX3)_15") (pintype "bidirectional"))
      (node (ref "RX") (pin "K") (pinfunction "C_K") (pintype "passive"))
      (node (ref "U$4") (pin "12") (pinfunction "R1_OUT_12") (pintype "bidirectional"))
    )
    (net (code "87") (name "Net-(PCB2-PadA0)") (class "Default")
      (node (ref "PCB2") (pin "A0") (pinfunction "A0_A0") (pintype "bidirectional"))
      (node (ref "R5") (pin "2") (pinfunction "2_2") (pintype "passive"))
    )
    (net (code "88") (name "Net-(PCB2-PadA1)") (class "Default")
      (node (ref "PCB2") (pin "A1") (pinfunction "A1_A1") (pintype "bidirectional"))
      (node (ref "R4") (pin "2") (pinfunction "2_2") (pintype "passive"))
    )
    (net (code "89") (name "Net-(PCB2-PadA2)") (class "Default")
      (node (ref "PCB2") (pin "A2") (pinfunction "A2_A2") (pintype "bidirectional"))
      (node (ref "R3") (pin "2") (pinfunction "2_2") (pintype "passive"))
    )
    (net (code "90") (name "Net-(PCB2-PadA3)") (class "Default")
      (node (ref "PCB2") (pin "A3") (pinfunction "A3_A3") (pintype "bidirectional"))
      (node (ref "R2") (pin "2") (pinfunction "2_2") (pintype "passive"))
    )
    (net (code "91") (name "Net-(Q1-D)") (class "Default")
      (node (ref "J2") (pin "2") (pinfunction "2_2") (pintype "passive"))
      (node (ref "J2") (pin "3") (pinfunction "3_3") (pintype "passive"))
      (node (ref "Q1") (pin "4") (pinfunction "D_4") (pintype "bidirectional"))
    )
    (net (code "92") (name "Net-(Q1-G)") (class "Default")
      (node (ref "Q1") (pin "1") (pinfunction "G_1") (pintype "bidirectional"))
      (node (ref "RFET") (pin "1") (pinfunction "1_1") (pintype "passive"))
    )
    (net (code "93") (name "Net-(R6-Pad1)") (class "Default")
      (node (ref "R6") (pin "1") (pinfunction "1_1") (pintype "passive"))
      (node (ref "U$3") (pin "SIGNAL") (pinfunction "SIGNAL_SIGNAL") (pintype "bidirectional"))
    )
    (net (code "94") (name "Net-(R7-Pad1)") (class "Default")
      (node (ref "R7") (pin "1") (pinfunction "1_1") (pintype "passive"))
      (node (ref "U$2") (pin "SIGNAL") (pinfunction "SIGNAL_SIGNAL") (pintype "bidirectional"))
    )
    (net (code "95") (name "Net-(R8-Pad2)") (class "Default")
      (node (ref "R8") (pin "2") (pinfunction "2_2") (pintype "passive"))
      (node (ref "U$8") (pin "SIGNAL") (pinfunction "SIGNAL_SIGNAL") (pintype "bidirectional"))
    )
    (net (code "96") (name "Net-(R9-Pad1)") (class "Default")
      (node (ref "R9") (pin "1") (pinfunction "1_1") (pintype "passive"))
      (node (ref "U$1") (pin "SIGNAL") (pinfunction "SIGNAL_SIGNAL") (pintype "bidirectional"))
    )
    (net (code "97") (name "Net-(R15-Pad2)") (class "Default")
      (node (ref "R15") (pin "2") (pinfunction "2_2") (pintype "passive"))
      (node (ref "TX") (pin "A") (pinfunction "A_A") (pintype "passive"))
    )
    (net (code "98") (name "Net-(R16-Pad2)") (class "Default")
      (node (ref "R16") (pin "2") (pinfunction "2_2") (pintype "passive"))
      (node (ref "RX") (pin "A") (pinfunction "A_A") (pintype "passive"))
    )
    (net (code "99") (name "Net-(TM1-S)") (class "Default")
      (node (ref "JP9") (pin "3") (pinfunction "3_3") (pintype "passive"))
      (node (ref "TM1") (pin "2") (pinfunction "S_2") (pintype "passive"))
    )
    (net (code "100") (name "Net-(U$4-R1_IN)") (class "Default")
      (node (ref "U$4") (pin "13") (pinfunction "R1_IN_13") (pintype "bidirectional"))
      (node (ref "X3") (pin "3") (pinfunction "3_3") (pintype "passive"))
    )
    (net (code "101") (name "Net-(U$4-T1_OUT)") (class "Default")
      (node (ref "U$4") (pin "14") (pinfunction "T1_OUT_14") (pintype "bidirectional"))
      (node (ref "X3") (pin "2") (pinfunction "2_2") (pintype "passive"))
    )
    (net (code "102") (name "Net-(X4--2)") (class "Default")
      (node (ref "R11") (pin "2") (pinfunction "2_2") (pintype "passive"))
      (node (ref "X4") (pin "A2") (pinfunction "-2_A2") (pintype "passive"))
      (node (ref "X4") (pin "B2") (pinfunction "B-2_B2") (pintype "passive"))
    )
    (net (code "103") (name "Net-(X4--4)") (class "Default")
      (node (ref "R12") (pin "2") (pinfunction "2_2") (pintype "passive"))
      (node (ref "X4") (pin "A4") (pinfunction "-4_A4") (pintype "passive"))
      (node (ref "X4") (pin "B4") (pinfunction "B-4_B4") (pintype "passive"))
    )
    (net (code "104") (name "Net-(X4-B-3)") (class "Default")
      (node (ref "R13") (pin "2") (pinfunction "2_2") (pintype "passive"))
      (node (ref "X4") (pin "B3") (pinfunction "B-3_B3") (pintype "passive"))
    )
    (net (code "105") (name "Net-(X4-B-5)") (class "Default")
      (node (ref "R14") (pin "2") (pinfunction "2_2") (pintype "passive"))
      (node (ref "X4") (pin "B5") (pinfunction "B-5_B5") (pintype "passive"))
    )
    (net (code "106") (name "Net-(X4-B-6)") (class "Default")
      (node (ref "R10") (pin "2") (pinfunction "2_2") (pintype "passive"))
      (node (ref "X4") (pin "B6") (pinfunction "B-6_B6") (pintype "passive"))
    )
    (net (code "107") (name "VCC") (class "Default")
      (node (ref "C1") (pin "2") (pinfunction "2_2") (pintype "passive"))
      (node (ref "C10") (pin "+") (pinfunction "+_+") (pintype "passive"))
      (node (ref "C11") (pin "+") (pinfunction "+_+") (pintype "passive"))
      (node (ref "C8") (pin "+") (pinfunction "+_+") (pintype "passive"))
      (node (ref "C9") (pin "+") (pinfunction "+_+") (pintype "passive"))
      (node (ref "M1") (pin "16") (pinfunction "VMOT_16") (pintype "power_in"))
      (node (ref "M2") (pin "16") (pinfunction "VMOT_16") (pintype "power_in"))
      (node (ref "M3") (pin "16") (pinfunction "VMOT_16") (pintype "power_in"))
      (node (ref "M4") (pin "16") (pinfunction "VMOT_16") (pintype "power_in"))
      (node (ref "PCB2") (pin "VIN") (pinfunction "VIN_VIN") (pintype "bidirectional"))
      (node (ref "U$5") (pin "P$3") (pinfunction "V78$V0_P$3") (pintype "bidirectional"))
      (node (ref "U2") (pin "VIN") (pinfunction "VIN_VIN") (pintype "bidirectional"))
    )
    (net (code "108") (name "unconnected-(JP9-Pad7)") (class "Default")
      (node (ref "JP9") (pin "7") (pinfunction "7_7") (pintype "passive"))
    )
    (net (code "109") (name "unconnected-(JP9-Pad8)") (class "Default")
      (node (ref "JP9") (pin "8") (pinfunction "8_8") (pintype "passive"))
    )
    (net (code "110") (name "unconnected-(JP9-Pad9)") (class "Default")
      (node (ref "JP9") (pin "9") (pinfunction "9_9") (pintype "passive"))
    )
    (net (code "111") (name "unconnected-(JP9-Pad10)") (class "Default")
      (node (ref "JP9") (pin "10") (pinfunction "10_10") (pintype "passive"))
    )
    (net (code "112") (name "unconnected-(PCB2-(N{slash}C)-PadN{slash}C)") (class "Default")
      (node (ref "PCB2") (pin "N/C") (pinfunction "(N/C)_N/C") (pintype "bidirectional"))
    )
    (net (code "113") (name "unconnected-(PCB2-+5V.-Pad5V.)") (class "Default")
      (node (ref "PCB2") (pin "5V.") (pinfunction "+5V._5V.") (pintype "bidirectional"))
    )
    (net (code "114") (name "unconnected-(PCB2-+5V..-Pad5V..)") (class "Default")
      (node (ref "PCB2") (pin "5V..") (pinfunction "+5V.._5V..") (pintype "bidirectional"))
    )
    (net (code "115") (name "unconnected-(PCB2-0(RX)-Pad0)") (class "Default")
      (node (ref "PCB2") (pin "0") (pinfunction "0(RX)_0") (pintype "bidirectional"))
    )
    (net (code "116") (name "unconnected-(PCB2-1(TX)-Pad1)") (class "Default")
      (node (ref "PCB2") (pin "1") (pinfunction "1(TX)_1") (pintype "bidirectional"))
    )
    (net (code "117") (name "unconnected-(PCB2-16(TX2)-Pad16)") (class "Default")
      (node (ref "PCB2") (pin "16") (pinfunction "16(TX2)_16") (pintype "bidirectional"))
    )
    (net (code "118") (name "unconnected-(PCB2-17(RX2)-Pad17)") (class "Default")
      (node (ref "PCB2") (pin "17") (pinfunction "17(RX2)_17") (pintype "bidirectional"))
    )
    (net (code "119") (name "unconnected-(PCB2-18(TX1)-Pad18)") (class "Default")
      (node (ref "PCB2") (pin "18") (pinfunction "18(TX1)_18") (pintype "bidirectional"))
    )
    (net (code "120") (name "unconnected-(PCB2-19(RX1)-Pad19)") (class "Default")
      (node (ref "PCB2") (pin "19") (pinfunction "19(RX1)_19") (pintype "bidirectional"))
    )
    (net (code "121") (name "unconnected-(PCB2-20(SDA)-Pad20)") (class "Default")
      (node (ref "PCB2") (pin "20") (pinfunction "20(SDA)_20") (pintype "bidirectional"))
    )
    (net (code "122") (name "unconnected-(PCB2-21(SCL)-Pad21)") (class "Default")
      (node (ref "PCB2") (pin "21") (pinfunction "21(SCL)_21") (pintype "bidirectional"))
    )
    (net (code "123") (name "unconnected-(PCB2-IOREF-PadI{slash}OREF)") (class "Default")
      (node (ref "PCB2") (pin "I/OREF") (pinfunction "IOREF_I/OREF") (pintype "bidirectional"))
    )
    (net (code "124") (name "unconnected-(PCB2-Pad+5V_)") (class "Default")
      (node (ref "PCB2") (pin "+5V_") (pinfunction "+5V__+5V_") (pintype "bidirectional"))
    )
    (net (code "125") (name "unconnected-(PCB2-Pad3.3V)") (class "Default")
      (node (ref "PCB2") (pin "3.3V") (pinfunction "3.3V_3.3V") (pintype "bidirectional"))
    )
    (net (code "126") (name "unconnected-(PCB2-Pad8)") (class "Default")
      (node (ref "PCB2") (pin "8") (pinfunction "8_8") (pintype "bidirectional"))
    )
    (net (code "127") (name "unconnected-(PCB2-Pad9)") (class "Default")
      (node (ref "PCB2") (pin "9") (pinfunction "9_9") (pintype "bidirectional"))
    )
    (net (code "128") (name "unconnected-(PCB2-Pad11)") (class "Default")
      (node (ref "PCB2") (pin "11") (pinfunction "11_11") (pintype "bidirectional"))
    )
    (net (code "129") (name "unconnected-(PCB2-Pad13)") (class "Default")
      (node (ref "PCB2") (pin "13") (pinfunction "13_13") (pintype "bidirectional"))
    )
    (net (code "130") (name "unconnected-(PCB2-Pad50)") (class "Default")
      (node (ref "PCB2") (pin "50") (pinfunction "50_50") (pintype "bidirectional"))
    )
    (net (code "131") (name "unconnected-(PCB2-Pad51)") (class "Default")
      (node (ref "PCB2") (pin "51") (pinfunction "51_51") (pintype "bidirectional"))
    )
    (net (code "132") (name "unconnected-(PCB2-Pad52)") (class "Default")
      (node (ref "PCB2") (pin "52") (pinfunction "52_52") (pintype "bidirectional"))
    )
    (net (code "133") (name "unconnected-(PCB2-PadAREF)") (class "Default")
      (node (ref "PCB2") (pin "AREF") (pinfunction "AREF_AREF") (pintype "bidirectional"))
    )
    (net (code "134") (name "unconnected-(PCB2-PadRESET.)") (class "Default")
      (node (ref "PCB2") (pin "RESET.") (pinfunction "RESET._RESET.") (pintype "bidirectional"))
    )
    (net (code "135") (name "unconnected-(PCB2-PadSCL1)") (class "Default")
      (node (ref "PCB2") (pin "SCL1") (pinfunction "SCL1_SCL1") (pintype "bidirectional"))
    )
    (net (code "136") (name "unconnected-(PCB2-PadSDA1)") (class "Default")
      (node (ref "PCB2") (pin "SDA1") (pinfunction "SDA1_SDA1") (pintype "bidirectional"))
    )
    (net (code "137") (name "unconnected-(U$4-R2_IN-Pad8)") (class "Default")
      (node (ref "U$4") (pin "8") (pinfunction "R2_IN_8") (pintype "bidirectional"))
    )
    (net (code "138") (name "unconnected-(U$4-R2_OUT-Pad9)") (class "Default")
      (node (ref "U$4") (pin "9") (pinfunction "R2_OUT_9") (pintype "bidirectional"))
    )
    (net (code "139") (name "unconnected-(U$4-T2_IN-Pad10)") (class "Default")
      (node (ref "U$4") (pin "10") (pinfunction "T2_IN_10") (pintype "bidirectional"))
    )
    (net (code "140") (name "unconnected-(U$4-T2_OUT-Pad7)") (class "Default")
      (node (ref "U$4") (pin "7") (pinfunction "T2_OUT_7") (pintype "bidirectional"))
    )
    (net (code "141") (name "unconnected-(U$6-SWTCH$2-PadSWITCH$2)") (class "Default")
      (node (ref "U$6") (pin "SWITCH$2") (pinfunction "SWTCH$2_SWITCH$2") (pintype "bidirectional"))
    )
    (net (code "142") (name "unconnected-(U2-*D3-PadD3)") (class "Default")
      (node (ref "U2") (pin "D3") (pinfunction "*D3_D3") (pintype "bidirectional"))
    )
    (net (code "143") (name "unconnected-(U2-*D5-PadD5)") (class "Default")
      (node (ref "U2") (pin "D5") (pinfunction "*D5_D5") (pintype "bidirectional"))
    )
    (net (code "144") (name "unconnected-(U2-*D6-PadD6)") (class "Default")
      (node (ref "U2") (pin "D6") (pinfunction "*D6_D6") (pintype "bidirectional"))
    )
    (net (code "145") (name "unconnected-(U2-*D9-PadD9)") (class "Default")
      (node (ref "U2") (pin "D9") (pinfunction "*D9_D9") (pintype "bidirectional"))
    )
    (net (code "146") (name "unconnected-(U2-GND-PadGND@2)") (class "Default")
      (node (ref "U2") (pin "GND@2") (pinfunction "GND_GND@2") (pintype "bidirectional"))
    )
    (net (code "147") (name "unconnected-(U2-Pad3.3V)") (class "Default")
      (node (ref "U2") (pin "3.3V") (pinfunction "3.3V_3.3V") (pintype "bidirectional"))
    )
    (net (code "148") (name "unconnected-(U2-PadA0)") (class "Default")
      (node (ref "U2") (pin "A0") (pinfunction "A0_A0") (pintype "bidirectional"))
    )
    (net (code "149") (name "unconnected-(U2-PadA1)") (class "Default")
      (node (ref "U2") (pin "A1") (pinfunction "A1_A1") (pintype "bidirectional"))
    )
    (net (code "150") (name "unconnected-(U2-PadA2)") (class "Default")
      (node (ref "U2") (pin "A2") (pinfunction "A2_A2") (pintype "bidirectional"))
    )
    (net (code "151") (name "unconnected-(U2-PadA3)") (class "Default")
      (node (ref "U2") (pin "A3") (pinfunction "A3_A3") (pintype "bidirectional"))
    )
    (net (code "152") (name "unconnected-(U2-PadA4)") (class "Default")
      (node (ref "U2") (pin "A4") (pinfunction "A4_A4") (pintype "bidirectional"))
    )
    (net (code "153") (name "unconnected-(U2-PadA5)") (class "Default")
      (node (ref "U2") (pin "A5") (pinfunction "A5_A5") (pintype "bidirectional"))
    )
    (net (code "154") (name "unconnected-(U2-PadAREF)") (class "Default")
      (node (ref "U2") (pin "AREF") (pinfunction "AREF_AREF") (pintype "bidirectional"))
    )
    (net (code "155") (name "unconnected-(U2-PadD2)") (class "Default")
      (node (ref "U2") (pin "D2") (pinfunction "D2_D2") (pintype "bidirectional"))
    )
    (net (code "156") (name "unconnected-(U2-PadD4)") (class "Default")
      (node (ref "U2") (pin "D4") (pinfunction "D4_D4") (pintype "bidirectional"))
    )
    (net (code "157") (name "unconnected-(U2-PadD8)") (class "Default")
      (node (ref "U2") (pin "D8") (pinfunction "D8_D8") (pintype "bidirectional"))
    )
    (net (code "158") (name "unconnected-(U2-PadRX)") (class "Default")
      (node (ref "U2") (pin "RX") (pinfunction "RX_RX") (pintype "bidirectional"))
    )
    (net (code "159") (name "unconnected-(U2-PadTX)") (class "Default")
      (node (ref "U2") (pin "TX") (pinfunction "TX_TX") (pintype "bidirectional"))
    )
    (net (code "160") (name "unconnected-(X3-Pad1)") (class "Default")
      (node (ref "X3") (pin "1") (pinfunction "1_1") (pintype "passive"))
    )
    (net (code "161") (name "unconnected-(X3-Pad4)") (class "Default")
      (node (ref "X3") (pin "4") (pinfunction "4_4") (pintype "passive"))
    )
    (net (code "162") (name "unconnected-(X3-Pad6)") (class "Default")
      (node (ref "X3") (pin "6") (pinfunction "6_6") (pintype "passive"))
    )
    (net (code "163") (name "unconnected-(X3-Pad7)") (class "Default")
      (node (ref "X3") (pin "7") (pinfunction "7_7") (pintype "passive"))
    )
    (net (code "164") (name "unconnected-(X3-Pad8)") (class "Default")
      (node (ref "X3") (pin "8") (pinfunction "8_8") (pintype "passive"))
    )
    (net (code "165") (name "unconnected-(X3-Pad9)") (class "Default")
      (node (ref "X3") (pin "9") (pinfunction "9_9") (pintype "passive"))
    )
    (net (code "166") (name "unconnected-(X4--1-PadA1)") (class "Default")
      (node (ref "X4") (pin "A1") (pinfunction "-1_A1") (pintype "passive"))
    )
    (net (code "167") (name "unconnected-(X4--3-PadA3)") (class "Default")
      (node (ref "X4") (pin "A3") (pinfunction "-3_A3") (pintype "passive"))
    )
    (net (code "168") (name "unconnected-(X4--5-PadA5)") (class "Default")
      (node (ref "X4") (pin "A5") (pinfunction "-5_A5") (pintype "passive"))
    )
    (net (code "169") (name "unconnected-(X4--6-PadA6)") (class "Default")
      (node (ref "X4") (pin "A6") (pinfunction "-6_A6") (pintype "passive"))
    )
  )
)
